# FPGAIO.net
KiCad netlist of a schematic drawn in Altium Designer
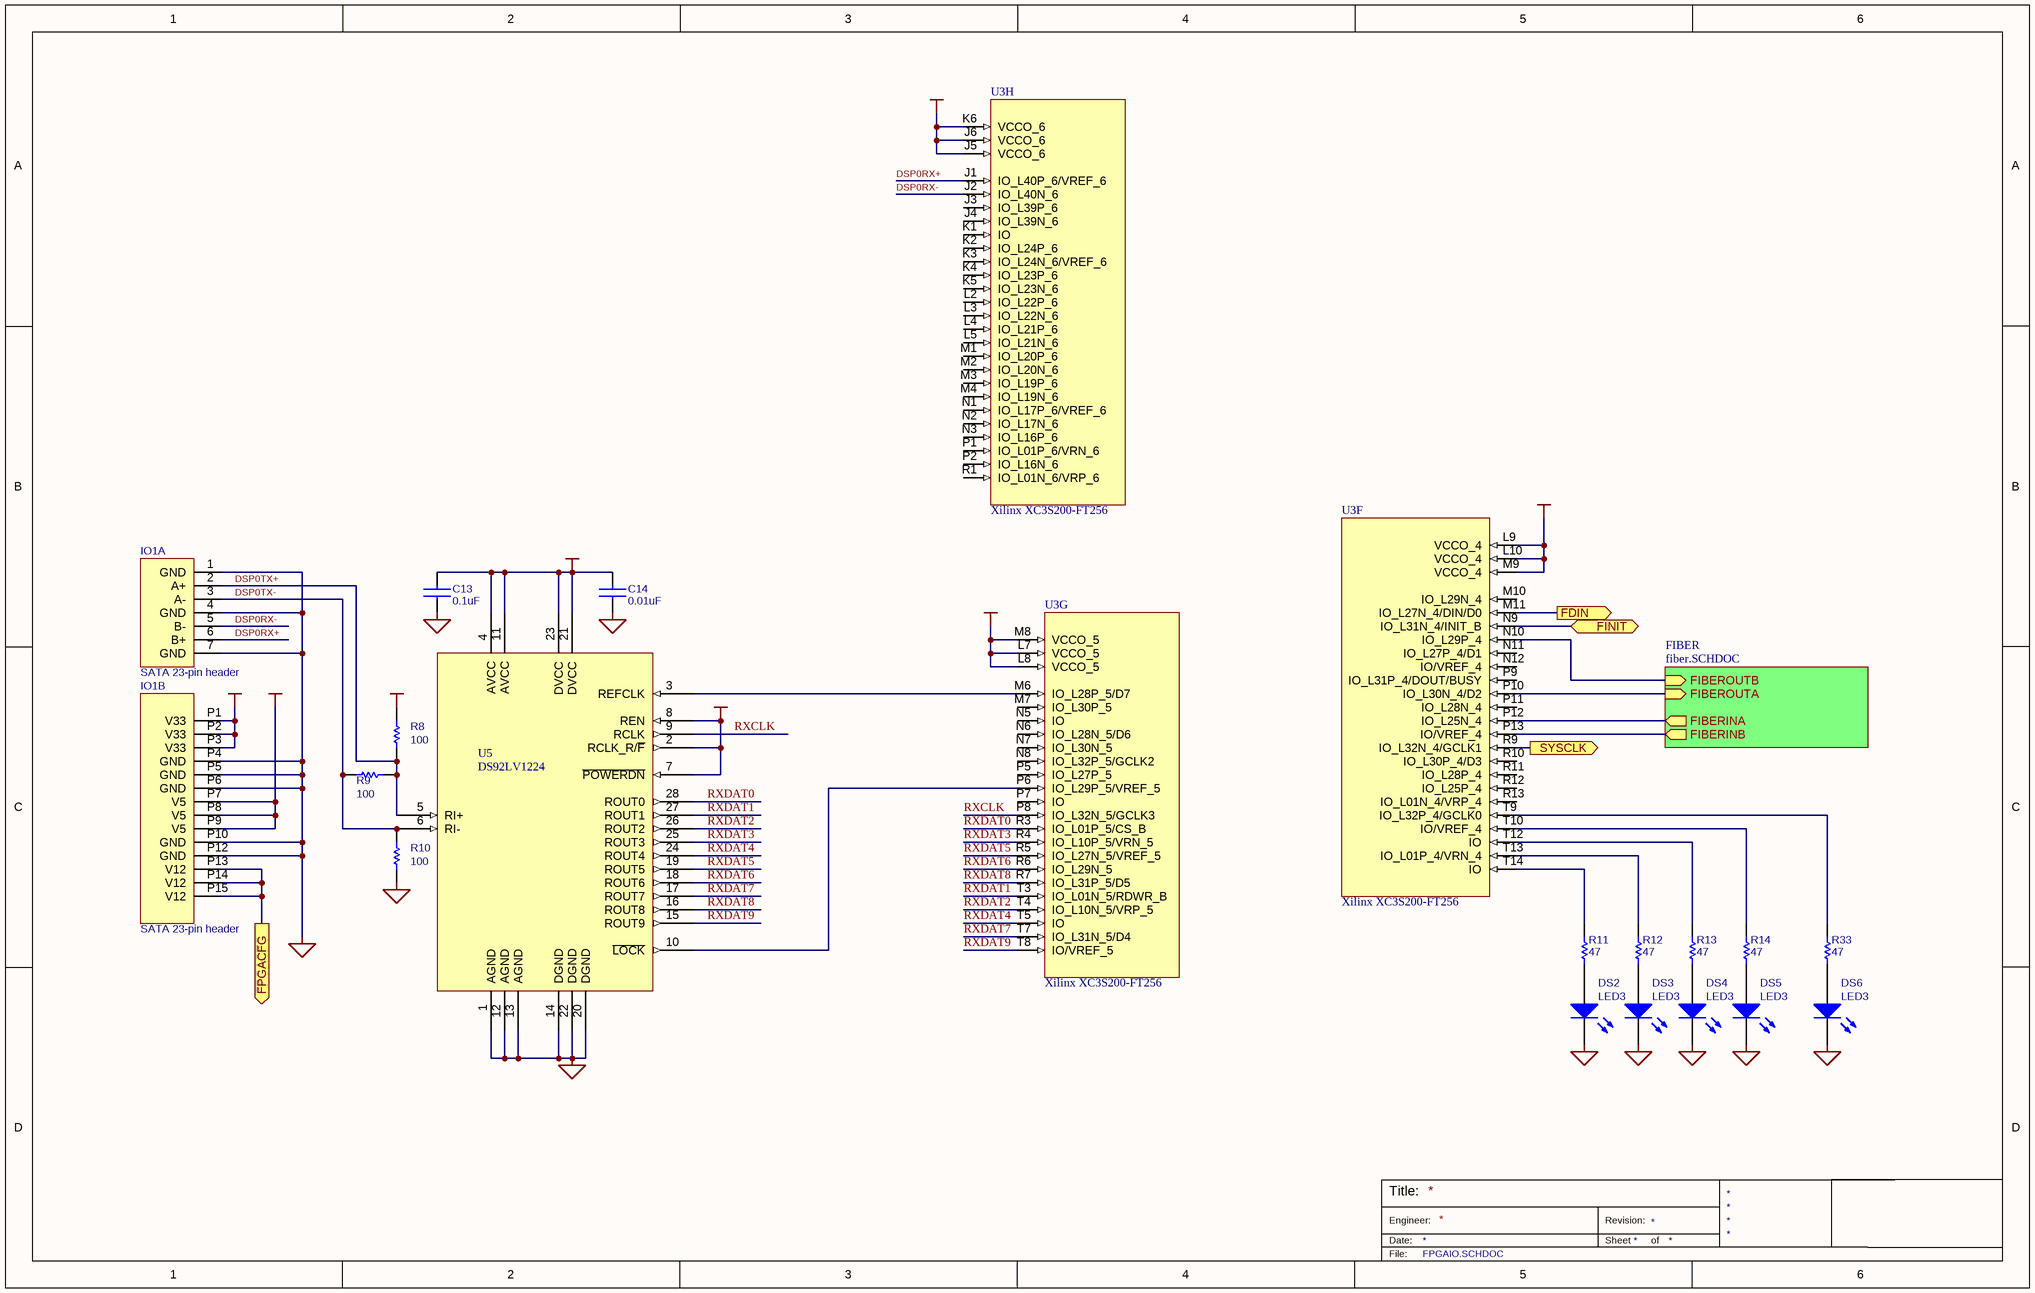
[diagram p0: FPGAIO.SCHDOC]

(export (version "E")
  (design (tool "Eeschema 10.0.6"))
  (components
    (comp (ref "C13")
      (value "0.1uF")
      (footprint "0603")
      (description "Standard Capacitor")
      (fields (field (name "Comment") "CAPACITOR"))
      (libsource (lib "parts") (part "CAPACITOR"))
    )
    (comp (ref "C14")
      (value "0.01uF")
      (footprint "0402")
      (description "Standard Capacitor")
      (fields (field (name "Comment") "CAPACITOR"))
      (libsource (lib "parts") (part "CAPACITOR"))
    )
    (comp (ref "DS2")
      (value "LED3")
      (footprint "LED0805")
      (description "Typical BLUE SiC LED")
      (fields (field (name "PUBLISHER") "Altium Limited"))
      (libsource (lib "Miscellaneous Devices") (part "LED3"))
    )
    (comp (ref "DS3")
      (value "LED3")
      (footprint "LED0805")
      (description "Typical BLUE SiC LED")
      (fields (field (name "PUBLISHER") "Altium Limited"))
      (libsource (lib "Miscellaneous Devices") (part "LED3"))
    )
    (comp (ref "DS4")
      (value "LED3")
      (footprint "LED0805")
      (description "Typical BLUE SiC LED")
      (fields (field (name "PUBLISHER") "Altium Limited"))
      (libsource (lib "Miscellaneous Devices") (part "LED3"))
    )
    (comp (ref "DS5")
      (value "LED3")
      (footprint "LED0805")
      (description "Typical BLUE SiC LED")
      (fields (field (name "PUBLISHER") "Altium Limited"))
      (libsource (lib "Miscellaneous Devices") (part "LED3"))
    )
    (comp (ref "DS6")
      (value "LED3")
      (footprint "LED0805")
      (description "Typical BLUE SiC LED")
      (fields (field (name "PUBLISHER") "Altium Limited"))
      (libsource (lib "Miscellaneous Devices") (part "LED3"))
    )
    (comp (ref "IO1")
      (value "SATA 23-pin header")
      (footprint "MOLEX 87703-0001")
      (description "Molex 1.27mm pitch SATA device Plug")
      (libsource (lib "parts") (part "SATA-23"))
    )
    (comp (ref "R8")
      (value "100")
      (footprint "0603")
      (description "Standard Passive Resistor")
      (libsource (lib "parts") (part "RESISTOR"))
    )
    (comp (ref "R9")
      (value "100")
      (footprint "0603")
      (description "Standard Passive Resistor")
      (libsource (lib "parts") (part "RESISTOR"))
    )
    (comp (ref "R10")
      (value "100")
      (footprint "0603")
      (description "Standard Passive Resistor")
      (libsource (lib "parts") (part "RESISTOR"))
    )
    (comp (ref "R11")
      (value "47")
      (footprint "0603")
      (description "Standard Passive Resistor")
      (fields (field (name "TOLERANCE") "1%") (field (name "Comment") "RESISTOR"))
      (libsource (lib "parts") (part "RESISTOR"))
    )
    (comp (ref "R12")
      (value "47")
      (footprint "0603")
      (description "Standard Passive Resistor")
      (fields (field (name "TOLERANCE") "1%") (field (name "Comment") "RESISTOR"))
      (libsource (lib "parts") (part "RESISTOR"))
    )
    (comp (ref "R13")
      (value "47")
      (footprint "0603")
      (description "Standard Passive Resistor")
      (fields (field (name "TOLERANCE") "1%") (field (name "Comment") "RESISTOR"))
      (libsource (lib "parts") (part "RESISTOR"))
    )
    (comp (ref "R14")
      (value "47")
      (footprint "0603")
      (description "Standard Passive Resistor")
      (fields (field (name "TOLERANCE") "1%") (field (name "Comment") "RESISTOR"))
      (libsource (lib "parts") (part "RESISTOR"))
    )
    (comp (ref "R33")
      (value "47")
      (footprint "0603")
      (description "Standard Passive Resistor")
      (fields (field (name "TOLERANCE") "1%") (field (name "Comment") "RESISTOR"))
      (libsource (lib "parts") (part "RESISTOR"))
    )
    (comp (ref "U3")
      (value "Xilinx XC3S200-FT256")
      (footprint "Xilinx FT256 BGA")
      (description "Xilinx Spartan-3 FPGA")
      (libsource (lib "parts") (part "XC3S200-FT256"))
    )
    (comp (ref "U5")
      (value "DS92LV1224")
      (footprint "SSO-G28/E4.3")
      (description "30-66 MHz 10-Bit Bus LVDS Deserializer")
      (libsource (lib "parts") (part "DS92LV1224"))
    )
  )
  (nets
    (net (code "1") (name "+2.5VCC") (class "Default")
      (node (ref "U3") (pin "J5") (pinfunction "VCCO_6_J5") (pintype "input"))
      (node (ref "U3") (pin "J6") (pinfunction "VCCO_6_J6") (pintype "input"))
      (node (ref "U3") (pin "K6") (pinfunction "VCCO_6_K6") (pintype "input"))
    )
    (net (code "2") (name "+5VCC") (class "Default")
      (node (ref "IO1") (pin "P7") (pinfunction "V5_P7") (pintype "passive"))
      (node (ref "IO1") (pin "P8") (pinfunction "V5_P8") (pintype "passive"))
      (node (ref "IO1") (pin "P9") (pinfunction "V5_P9") (pintype "passive"))
    )
    (net (code "3") (name "/DSP0RX+") (class "Default")
      (node (ref "IO1") (pin "6") (pinfunction "B+_6") (pintype "passive"))
      (node (ref "U3") (pin "J1") (pinfunction "IO_L40P_6/VREF_6_J1") (pintype "input"))
    )
    (net (code "4") (name "/DSP0RX-") (class "Default")
      (node (ref "IO1") (pin "5") (pinfunction "B-_5") (pintype "passive"))
      (node (ref "U3") (pin "J2") (pinfunction "IO_L40N_6_J2") (pintype "input"))
    )
    (net (code "5") (name "/DSP0TX+") (class "Default")
      (node (ref "IO1") (pin "2") (pinfunction "A+_2") (pintype "passive"))
      (node (ref "R8") (pin "2") (pintype "passive"))
      (node (ref "R9") (pin "2") (pintype "passive"))
      (node (ref "U5") (pin "5") (pinfunction "RI+_5") (pintype "input"))
    )
    (net (code "6") (name "/DSP0TX-") (class "Default")
      (node (ref "IO1") (pin "3") (pinfunction "A-_3") (pintype "passive"))
      (node (ref "R10") (pin "2") (pintype "passive"))
      (node (ref "R9") (pin "1") (pintype "passive"))
      (node (ref "U5") (pin "6") (pinfunction "RI-_6") (pintype "input"))
    )
    (net (code "7") (name "/FDIN") (class "Default")
      (node (ref "U3") (pin "M11") (pinfunction "IO_L27N_4/DIN/D0_M11") (pintype "input"))
    )
    (net (code "8") (name "/FIBERINA") (class "Default")
      (node (ref "U3") (pin "P12") (pinfunction "IO_L25N_4_P12") (pintype "input"))
    )
    (net (code "9") (name "/FIBERINB") (class "Default")
      (node (ref "U3") (pin "P13") (pinfunction "IO/VREF_4_P13") (pintype "input"))
    )
    (net (code "10") (name "/FIBEROUTA") (class "Default")
      (node (ref "U3") (pin "P10") (pinfunction "IO_L30N_4/D2_P10") (pintype "input"))
    )
    (net (code "11") (name "/FIBEROUTB") (class "Default")
      (node (ref "U3") (pin "N10") (pinfunction "IO_L29P_4_N10") (pintype "input"))
    )
    (net (code "12") (name "/FINIT") (class "Default")
      (node (ref "U3") (pin "N9") (pinfunction "IO_L31N_4/INIT_B_N9") (pintype "input"))
    )
    (net (code "13") (name "/FPGACFG") (class "Default")
      (node (ref "IO1") (pin "P13") (pinfunction "V12_P13") (pintype "passive"))
      (node (ref "IO1") (pin "P14") (pinfunction "V12_P14") (pintype "passive"))
      (node (ref "IO1") (pin "P15") (pinfunction "V12_P15") (pintype "passive"))
    )
    (net (code "14") (name "/RXCLK") (class "Default")
      (node (ref "U3") (pin "P8") (pinfunction "IO_L32N_5/GCLK3_P8") (pintype "input"))
      (node (ref "U5") (pin "9") (pinfunction "RCLK_9") (pintype "output"))
    )
    (net (code "15") (name "/RXDAT0") (class "Default")
      (node (ref "U3") (pin "R3") (pinfunction "IO_L01P_5/CS_B_R3") (pintype "input"))
      (node (ref "U5") (pin "28") (pinfunction "ROUT0_28") (pintype "output"))
    )
    (net (code "16") (name "/RXDAT1") (class "Default")
      (node (ref "U3") (pin "T3") (pinfunction "IO_L01N_5/RDWR_B_T3") (pintype "input"))
      (node (ref "U5") (pin "27") (pinfunction "ROUT1_27") (pintype "output"))
    )
    (net (code "17") (name "/RXDAT2") (class "Default")
      (node (ref "U3") (pin "T4") (pinfunction "IO_L10N_5/VRP_5_T4") (pintype "input"))
      (node (ref "U5") (pin "26") (pinfunction "ROUT2_26") (pintype "output"))
    )
    (net (code "18") (name "/RXDAT3") (class "Default")
      (node (ref "U3") (pin "R4") (pinfunction "IO_L10P_5/VRN_5_R4") (pintype "input"))
      (node (ref "U5") (pin "25") (pinfunction "ROUT3_25") (pintype "output"))
    )
    (net (code "19") (name "/RXDAT4") (class "Default")
      (node (ref "U3") (pin "T5") (pinfunction "IO_T5") (pintype "input"))
      (node (ref "U5") (pin "24") (pinfunction "ROUT4_24") (pintype "output"))
    )
    (net (code "20") (name "/RXDAT5") (class "Default")
      (node (ref "U3") (pin "R5") (pinfunction "IO_L27N_5/VREF_5_R5") (pintype "input"))
      (node (ref "U5") (pin "19") (pinfunction "ROUT5_19") (pintype "output"))
    )
    (net (code "21") (name "/RXDAT6") (class "Default")
      (node (ref "U3") (pin "R6") (pinfunction "IO_L29N_5_R6") (pintype "input"))
      (node (ref "U5") (pin "18") (pinfunction "ROUT6_18") (pintype "output"))
    )
    (net (code "22") (name "/RXDAT7") (class "Default")
      (node (ref "U3") (pin "T7") (pinfunction "IO_L31N_5/D4_T7") (pintype "input"))
      (node (ref "U5") (pin "17") (pinfunction "ROUT7_17") (pintype "output"))
    )
    (net (code "23") (name "/RXDAT8") (class "Default")
      (node (ref "U3") (pin "R7") (pinfunction "IO_L31P_5/D5_R7") (pintype "input"))
      (node (ref "U5") (pin "16") (pinfunction "ROUT8_16") (pintype "output"))
    )
    (net (code "24") (name "/RXDAT9") (class "Default")
      (node (ref "U3") (pin "T8") (pinfunction "IO/VREF_5_T8") (pintype "input"))
      (node (ref "U5") (pin "15") (pinfunction "ROUT9_15") (pintype "output"))
    )
    (net (code "25") (name "/SYSCLK") (class "Default")
      (node (ref "U3") (pin "R9") (pinfunction "IO_L32N_4/GCLK1_R9") (pintype "input"))
    )
    (net (code "26") (name "GND") (class "Default")
      (node (ref "C13") (pin "1") (pintype "passive"))
      (node (ref "C14") (pin "1") (pintype "passive"))
      (node (ref "DS2") (pin "2") (pinfunction "K_2") (pintype "passive"))
      (node (ref "DS3") (pin "2") (pinfunction "K_2") (pintype "passive"))
      (node (ref "DS4") (pin "2") (pinfunction "K_2") (pintype "passive"))
      (node (ref "DS5") (pin "2") (pinfunction "K_2") (pintype "passive"))
      (node (ref "DS6") (pin "2") (pinfunction "K_2") (pintype "passive"))
      (node (ref "IO1") (pin "1") (pinfunction "GND_1") (pintype "passive"))
      (node (ref "IO1") (pin "4") (pinfunction "GND_4") (pintype "passive"))
      (node (ref "IO1") (pin "7") (pinfunction "GND_7") (pintype "passive"))
      (node (ref "IO1") (pin "P10") (pinfunction "GND_P10") (pintype "passive"))
      (node (ref "IO1") (pin "P12") (pinfunction "GND_P12") (pintype "passive"))
      (node (ref "IO1") (pin "P4") (pinfunction "GND_P4") (pintype "passive"))
      (node (ref "IO1") (pin "P5") (pinfunction "GND_P5") (pintype "passive"))
      (node (ref "IO1") (pin "P6") (pinfunction "GND_P6") (pintype "passive"))
      (node (ref "R10") (pin "1") (pintype "passive"))
      (node (ref "U5") (pin "1") (pinfunction "AGND_1") (pintype "power_in"))
      (node (ref "U5") (pin "12") (pinfunction "AGND_12") (pintype "power_in"))
      (node (ref "U5") (pin "13") (pinfunction "AGND_13") (pintype "power_in"))
      (node (ref "U5") (pin "14") (pinfunction "DGND_14") (pintype "power_in"))
      (node (ref "U5") (pin "20") (pinfunction "DGND_20") (pintype "power_in"))
      (node (ref "U5") (pin "22") (pinfunction "DGND_22") (pintype "power_in"))
    )
    (net (code "27") (name "Net-(DS2-A)") (class "Default")
      (node (ref "DS2") (pin "1") (pinfunction "A_1") (pintype "passive"))
      (node (ref "R11") (pin "2") (pintype "passive"))
    )
    (net (code "28") (name "Net-(DS3-A)") (class "Default")
      (node (ref "DS3") (pin "1") (pinfunction "A_1") (pintype "passive"))
      (node (ref "R12") (pin "2") (pintype "passive"))
    )
    (net (code "29") (name "Net-(DS4-A)") (class "Default")
      (node (ref "DS4") (pin "1") (pinfunction "A_1") (pintype "passive"))
      (node (ref "R13") (pin "2") (pintype "passive"))
    )
    (net (code "30") (name "Net-(DS5-A)") (class "Default")
      (node (ref "DS5") (pin "1") (pinfunction "A_1") (pintype "passive"))
      (node (ref "R14") (pin "2") (pintype "passive"))
    )
    (net (code "31") (name "Net-(DS6-A)") (class "Default")
      (node (ref "DS6") (pin "1") (pinfunction "A_1") (pintype "passive"))
      (node (ref "R33") (pin "2") (pintype "passive"))
    )
    (net (code "32") (name "Net-(R11-Pad1)") (class "Default")
      (node (ref "R11") (pin "1") (pintype "passive"))
      (node (ref "U3") (pin "T14") (pinfunction "IO_T14") (pintype "input"))
    )
    (net (code "33") (name "Net-(R13-Pad1)") (class "Default")
      (node (ref "R13") (pin "1") (pintype "passive"))
      (node (ref "U3") (pin "T12") (pinfunction "IO_T12") (pintype "input"))
    )
    (net (code "34") (name "Net-(R14-Pad1)") (class "Default")
      (node (ref "R14") (pin "1") (pintype "passive"))
      (node (ref "U3") (pin "T10") (pinfunction "IO/VREF_4_T10") (pintype "input"))
    )
    (net (code "35") (name "Net-(U3F-IO_L01P_4{slash}VRN_4)") (class "Default")
      (node (ref "R12") (pin "1") (pintype "passive"))
      (node (ref "U3") (pin "T13") (pinfunction "IO_L01P_4/VRN_4_T13") (pintype "input"))
    )
    (net (code "36") (name "Net-(U3F-IO_L32P_4{slash}GCLK0)") (class "Default")
      (node (ref "R33") (pin "1") (pintype "passive"))
      (node (ref "U3") (pin "T9") (pinfunction "IO_L32P_4/GCLK0_T9") (pintype "input"))
    )
    (net (code "37") (name "Net-(U3G-IO_L28P_5{slash}D7)") (class "Default")
      (node (ref "U3") (pin "M6") (pinfunction "IO_L28P_5/D7_M6") (pintype "input"))
      (node (ref "U5") (pin "3") (pinfunction "REFCLK_3") (pintype "input"))
    )
    (net (code "38") (name "Net-(U3G-IO_L29P_5{slash}VREF_5)") (class "Default")
      (node (ref "U3") (pin "P6") (pinfunction "IO_L29P_5/VREF_5_P6") (pintype "input"))
      (node (ref "U5") (pin "10") (pinfunction "~{LOCK}_10") (pintype "output"))
    )
    (net (code "39") (name "VCC") (class "Default")
      (node (ref "C13") (pin "2") (pintype "passive"))
      (node (ref "C14") (pin "2") (pintype "passive"))
      (node (ref "IO1") (pin "P1") (pinfunction "V33_P1") (pintype "passive"))
      (node (ref "IO1") (pin "P2") (pinfunction "V33_P2") (pintype "passive"))
      (node (ref "IO1") (pin "P3") (pinfunction "V33_P3") (pintype "passive"))
      (node (ref "R8") (pin "1") (pintype "passive"))
      (node (ref "U3") (pin "L10") (pinfunction "VCCO_4_L10") (pintype "input"))
      (node (ref "U3") (pin "L7") (pinfunction "VCCO_5_L7") (pintype "input"))
      (node (ref "U3") (pin "L8") (pinfunction "VCCO_5_L8") (pintype "input"))
      (node (ref "U3") (pin "L9") (pinfunction "VCCO_4_L9") (pintype "input"))
      (node (ref "U3") (pin "M8") (pinfunction "VCCO_5_M8") (pintype "input"))
      (node (ref "U3") (pin "M9") (pinfunction "VCCO_4_M9") (pintype "input"))
      (node (ref "U5") (pin "11") (pinfunction "AVCC_11") (pintype "power_in"))
      (node (ref "U5") (pin "2") (pinfunction "RCLK_R/~{F}_2") (pintype "output"))
      (node (ref "U5") (pin "21") (pinfunction "DVCC_21") (pintype "power_in"))
      (node (ref "U5") (pin "23") (pinfunction "DVCC_23") (pintype "power_in"))
      (node (ref "U5") (pin "4") (pinfunction "AVCC_4") (pintype "power_in"))
      (node (ref "U5") (pin "7") (pinfunction "~{POWERDN}_7") (pintype "input"))
      (node (ref "U5") (pin "8") (pinfunction "REN_8") (pintype "input"))
    )
    (net (code "40") (name "unconnected-(U3F-IO_L01N_4{slash}VRP_4-PadR13)") (class "Default")
      (node (ref "U3") (pin "R13") (pinfunction "IO_L01N_4/VRP_4_R13") (pintype "input"))
    )
    (net (code "41") (name "unconnected-(U3F-IO_L25P_4-PadR12)") (class "Default")
      (node (ref "U3") (pin "R12") (pinfunction "IO_L25P_4_R12") (pintype "input"))
    )
    (net (code "42") (name "unconnected-(U3F-IO_L27P_4{slash}D1-PadN11)") (class "Default")
      (node (ref "U3") (pin "N11") (pinfunction "IO_L27P_4/D1_N11") (pintype "input"))
    )
    (net (code "43") (name "unconnected-(U3F-IO_L28N_4-PadP11)") (class "Default")
      (node (ref "U3") (pin "P11") (pinfunction "IO_L28N_4_P11") (pintype "input"))
    )
    (net (code "44") (name "unconnected-(U3F-IO_L28P_4-PadR11)") (class "Default")
      (node (ref "U3") (pin "R11") (pinfunction "IO_L28P_4_R11") (pintype "input"))
    )
    (net (code "45") (name "unconnected-(U3F-IO_L29N_4-PadM10)") (class "Default")
      (node (ref "U3") (pin "M10") (pinfunction "IO_L29N_4_M10") (pintype "input"))
    )
    (net (code "46") (name "unconnected-(U3F-IO_L30P_4{slash}D3-PadR10)") (class "Default")
      (node (ref "U3") (pin "R10") (pinfunction "IO_L30P_4/D3_R10") (pintype "input"))
    )
    (net (code "47") (name "unconnected-(U3F-IO_L31P_4{slash}DOUT{slash}BUSY-PadP9)") (class "Default")
      (node (ref "U3") (pin "P9") (pinfunction "IO_L31P_4/DOUT/BUSY_P9") (pintype "input"))
    )
    (net (code "48") (name "unconnected-(U3F-IO{slash}VREF_4-PadN12)") (class "Default")
      (node (ref "U3") (pin "N12") (pinfunction "IO/VREF_4_N12") (pintype "input"))
    )
    (net (code "49") (name "unconnected-(U3G-IO-PadN5)") (class "Default")
      (node (ref "U3") (pin "N5") (pinfunction "IO_N5") (pintype "input"))
    )
    (net (code "50") (name "unconnected-(U3G-IO-PadP7)") (class "Default")
      (node (ref "U3") (pin "P7") (pinfunction "IO_P7") (pintype "input"))
    )
    (net (code "51") (name "unconnected-(U3G-IO_L27P_5-PadP5)") (class "Default")
      (node (ref "U3") (pin "P5") (pinfunction "IO_L27P_5_P5") (pintype "input"))
    )
    (net (code "52") (name "unconnected-(U3G-IO_L28N_5{slash}D6-PadN6)") (class "Default")
      (node (ref "U3") (pin "N6") (pinfunction "IO_L28N_5/D6_N6") (pintype "input"))
    )
    (net (code "53") (name "unconnected-(U3G-IO_L30N_5-PadN7)") (class "Default")
      (node (ref "U3") (pin "N7") (pinfunction "IO_L30N_5_N7") (pintype "input"))
    )
    (net (code "54") (name "unconnected-(U3G-IO_L30P_5-PadM7)") (class "Default")
      (node (ref "U3") (pin "M7") (pinfunction "IO_L30P_5_M7") (pintype "input"))
    )
    (net (code "55") (name "unconnected-(U3G-IO_L32P_5{slash}GCLK2-PadN8)") (class "Default")
      (node (ref "U3") (pin "N8") (pinfunction "IO_L32P_5/GCLK2_N8") (pintype "input"))
    )
    (net (code "56") (name "unconnected-(U3H-IO-PadK1)") (class "Default")
      (node (ref "U3") (pin "K1") (pinfunction "IO_K1") (pintype "input"))
    )
    (net (code "57") (name "unconnected-(U3H-IO_L01N_6{slash}VRP_6-PadR1)") (class "Default")
      (node (ref "U3") (pin "R1") (pinfunction "IO_L01N_6/VRP_6_R1") (pintype "input"))
    )
    (net (code "58") (name "unconnected-(U3H-IO_L01P_6{slash}VRN_6-PadP1)") (class "Default")
      (node (ref "U3") (pin "P1") (pinfunction "IO_L01P_6/VRN_6_P1") (pintype "input"))
    )
    (net (code "59") (name "unconnected-(U3H-IO_L16N_6-PadP2)") (class "Default")
      (node (ref "U3") (pin "P2") (pinfunction "IO_L16N_6_P2") (pintype "input"))
    )
    (net (code "60") (name "unconnected-(U3H-IO_L16P_6-PadN3)") (class "Default")
      (node (ref "U3") (pin "N3") (pinfunction "IO_L16P_6_N3") (pintype "input"))
    )
    (net (code "61") (name "unconnected-(U3H-IO_L17N_6-PadN2)") (class "Default")
      (node (ref "U3") (pin "N2") (pinfunction "IO_L17N_6_N2") (pintype "input"))
    )
    (net (code "62") (name "unconnected-(U3H-IO_L17P_6{slash}VREF_6-PadN1)") (class "Default")
      (node (ref "U3") (pin "N1") (pinfunction "IO_L17P_6/VREF_6_N1") (pintype "input"))
    )
    (net (code "63") (name "unconnected-(U3H-IO_L19N_6-PadM4)") (class "Default")
      (node (ref "U3") (pin "M4") (pinfunction "IO_L19N_6_M4") (pintype "input"))
    )
    (net (code "64") (name "unconnected-(U3H-IO_L19P_6-PadM3)") (class "Default")
      (node (ref "U3") (pin "M3") (pinfunction "IO_L19P_6_M3") (pintype "input"))
    )
    (net (code "65") (name "unconnected-(U3H-IO_L20N_6-PadM2)") (class "Default")
      (node (ref "U3") (pin "M2") (pinfunction "IO_L20N_6_M2") (pintype "input"))
    )
    (net (code "66") (name "unconnected-(U3H-IO_L20P_6-PadM1)") (class "Default")
      (node (ref "U3") (pin "M1") (pinfunction "IO_L20P_6_M1") (pintype "input"))
    )
    (net (code "67") (name "unconnected-(U3H-IO_L21N_6-PadL5)") (class "Default")
      (node (ref "U3") (pin "L5") (pinfunction "IO_L21N_6_L5") (pintype "input"))
    )
    (net (code "68") (name "unconnected-(U3H-IO_L21P_6-PadL4)") (class "Default")
      (node (ref "U3") (pin "L4") (pinfunction "IO_L21P_6_L4") (pintype "input"))
    )
    (net (code "69") (name "unconnected-(U3H-IO_L22N_6-PadL3)") (class "Default")
      (node (ref "U3") (pin "L3") (pinfunction "IO_L22N_6_L3") (pintype "input"))
    )
    (net (code "70") (name "unconnected-(U3H-IO_L22P_6-PadL2)") (class "Default")
      (node (ref "U3") (pin "L2") (pinfunction "IO_L22P_6_L2") (pintype "input"))
    )
    (net (code "71") (name "unconnected-(U3H-IO_L23N_6-PadK5)") (class "Default")
      (node (ref "U3") (pin "K5") (pinfunction "IO_L23N_6_K5") (pintype "input"))
    )
    (net (code "72") (name "unconnected-(U3H-IO_L23P_6-PadK4)") (class "Default")
      (node (ref "U3") (pin "K4") (pinfunction "IO_L23P_6_K4") (pintype "input"))
    )
    (net (code "73") (name "unconnected-(U3H-IO_L24N_6{slash}VREF_6-PadK3)") (class "Default")
      (node (ref "U3") (pin "K3") (pinfunction "IO_L24N_6/VREF_6_K3") (pintype "input"))
    )
    (net (code "74") (name "unconnected-(U3H-IO_L24P_6-PadK2)") (class "Default")
      (node (ref "U3") (pin "K2") (pinfunction "IO_L24P_6_K2") (pintype "input"))
    )
    (net (code "75") (name "unconnected-(U3H-IO_L39N_6-PadJ4)") (class "Default")
      (node (ref "U3") (pin "J4") (pinfunction "IO_L39N_6_J4") (pintype "input"))
    )
    (net (code "76") (name "unconnected-(U3H-IO_L39P_6-PadJ3)") (class "Default")
      (node (ref "U3") (pin "J3") (pinfunction "IO_L39P_6_J3") (pintype "input"))
    )
  )
)
